# pcbSchematic.net
KiCad netlist of a schematic drawn in Altium Designer
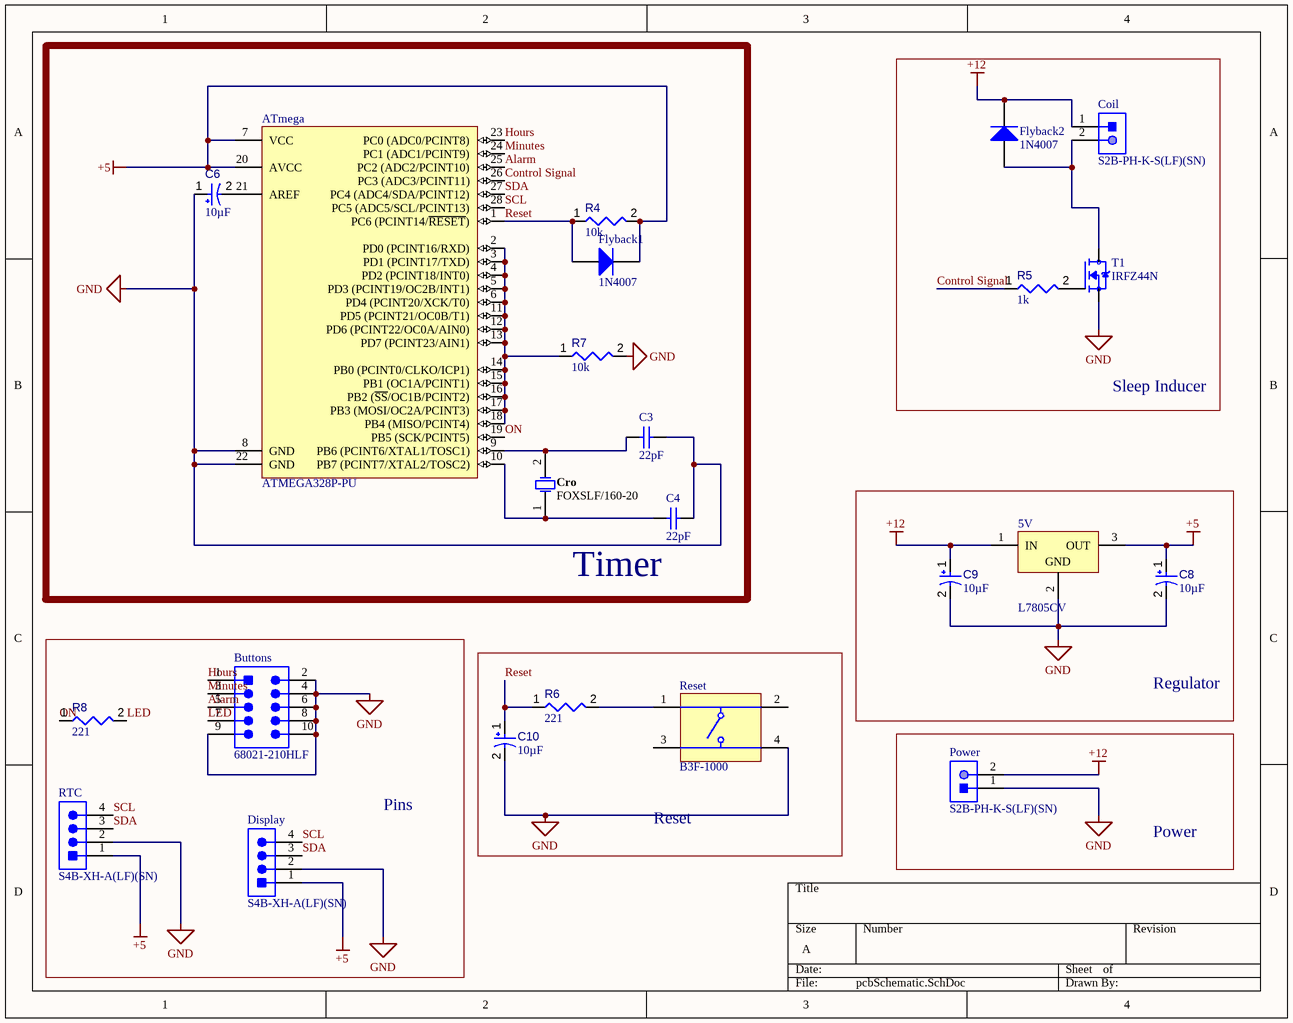
[diagram p0: pcbSchematic.SchDoc]

(export (version "E")
  (design (tool "Eeschema 10.0.6"))
  (components
    (comp (ref "5V")
      (value "L7805CV")
      (footprint "TO220")
      (description "Positive Voltage Regulator IC, 1.5 A, 5 V, 0 to 125 degC, 3-Pin TO-220, RoHS, Tube")
      (fields (field (name "MANUFACTURER") "STMicroelectronics"))
      (libsource (lib "Sithma") (part "PM-REG-L4940-SIL3"))
    )
    (comp (ref "ATmega")
      (value "ATMEGA328P-PU")
      (footprint "ATML-28P3")
      (fields (field (name "MANUFACTURER") "Atmel"))
      (libsource (lib "Sithma") (part "MC-8B-ATM48-IL28"))
    )
    (comp (ref "Buttons")
      (value "68021-210HLF")
      (footprint "FCI-68021-210HLF-10_V")
      (description "Male Header, Pitch 2.54 mm, 2 x 5 Position, Height 4.83 mm, Tail Length 3.05 mm, Bulk")
      (fields (field (name "MANUFACTURER") "FCI Electronics"))
      (libsource (lib "Sithma") (part "CN-2P-M-R10"))
    )
    (comp (ref "C3")
      (value "22pF")
      (footprint "KEMT-C315-THT-2")
      (description "Capacitor, Ceramic, 22 pF, +/-10 %, 100 V, -55 to 125 degC, 2-Pin THD, RoHS, Bulk")
      (libsource (lib "Altium Content Vault") (part "CAP-NP-2"))
    )
    (comp (ref "C4")
      (value "22pF")
      (footprint "KEMT-C315-THT-2")
      (description "Capacitor, Ceramic, 22 pF, +/-10 %, 100 V, -55 to 125 degC, 2-Pin THD, RoHS, Bulk")
      (libsource (lib "Altium Content Vault") (part "CAP-NP-2"))
    )
    (comp (ref "C6")
      (value "10µF")
      (footprint "CAPPR55-200-1100X500X1200")
      (description "Aluminum Electrolytic Capacitor, 10 uF, +/- 20%, 50 V, -40 to 85 degC, 2-Pin THD, RoHS, Bulk")
      (fields (field (name "MANUFACTURER") "Panasonic") (field (name "TOLERANCE") "20%"))
      (libsource (lib "") (part "CAP-P-2_1"))
    )
    (comp (ref "C8")
      (value "10µF")
      (footprint "CAPPR55-200-1100X500X1200")
      (description "Aluminum Electrolytic Capacitor, 10 uF, +/- 20%, 50 V, -40 to 85 degC, 2-Pin THD, RoHS, Bulk")
      (fields (field (name "MANUFACTURER") "Panasonic") (field (name "TOLERANCE") "20%"))
      (libsource (lib "Sithma") (part "CAP-P-2"))
    )
    (comp (ref "C9")
      (value "10µF")
      (footprint "CAPPR55-200-1100X500X1200")
      (description "Aluminum Electrolytic Capacitor, 10 uF, +/- 20%, 50 V, -40 to 85 degC, 2-Pin THD, RoHS, Bulk")
      (fields (field (name "MANUFACTURER") "Panasonic") (field (name "TOLERANCE") "20%"))
      (libsource (lib "Sithma") (part "CAP-P-2"))
    )
    (comp (ref "C10")
      (value "10µF")
      (footprint "CAPPR55-200-1100X500X1200")
      (description "Aluminum Electrolytic Capacitor, 10 uF, +/- 20%, 50 V, -40 to 85 degC, 2-Pin THD, RoHS, Bulk")
      (fields (field (name "MANUFACTURER") "Panasonic") (field (name "TOLERANCE") "20%"))
      (libsource (lib "Sithma") (part "CAP-P-2"))
    )
    (comp (ref "Coil")
      (value "S2B-PH-K-S(LF)(SN)")
      (footprint "JST-S2B-PH-K-S_V")
      (fields (field (name "MANUFACTURER") "Japan Solderless Terminals"))
      (libsource (lib "Sithma") (part "CN-1P-M-R2"))
    )
    (comp (ref "Cro")
      (value "FOXSLF/160-20")
      (footprint "FOX-FOXSLF160-20")
      (fields (field (name "MANUFACTURER") "FOX Electronics") (field (name "TOLERANCE") "50ppm"))
      (libsource (lib "Sithma") (part "XTAL-1-2-2"))
    )
    (comp (ref "Display")
      (value "S4B-XH-A(LF)(SN)")
      (footprint "JST-S4B-XH-A(LF)(SN)_V")
      (fields (field (name "MANUFACTURER") "JST"))
      (libsource (lib "Sithma") (part "CN-1P-M-R4"))
    )
    (comp (ref "Flyback1")
      (value "1N4007")
      (footprint "FAIR-DO-41-2")
      (description "General Purpose Rectifier, 1.1 V, 1.0 A, -55 to 175 degC, 2-Pin DO-41, RoHS, Tape and Reel")
      (fields (field (name "MANUFACTURER") "Fairchild"))
      (libsource (lib "Sithma") (part "KESE-D_K1A2-2"))
    )
    (comp (ref "Flyback2")
      (value "1N4007")
      (footprint "FAIR-DO-41-2")
      (description "General Purpose Rectifier, 1.1 V, 1.0 A, -55 to 175 degC, 2-Pin DO-41, RoHS, Tape and Reel")
      (fields (field (name "MANUFACTURER") "Fairchild"))
      (libsource (lib "Sithma") (part "KESE-D_K1A2-2"))
    )
    (comp (ref "Power")
      (value "S2B-PH-K-S(LF)(SN)")
      (footprint "JST-S2B-PH-K-S_V")
      (fields (field (name "MANUFACTURER") "Japan Solderless Terminals"))
      (libsource (lib "") (part "CN-1P-M-R2_1"))
    )
    (comp (ref "R4")
      (value "10k")
      (footprint "RESA60-630X240")
      (description "Axial Resistor, 10 KOhm, +/- 1%, 0.25 W, -55 to 155 degC, 2-Pin THD, RoHS, Bulk")
      (fields (field (name "TOLERANCE") "1%") (field (name "POWER") "250mW"))
      (libsource (lib "Sithma") (part "RES-2"))
    )
    (comp (ref "R5")
      (value "1k")
      (footprint "RESA60-630X240")
      (description "Axial Resistor, 1 KOhm, +/- 1%, 250 mW, -55 to 155 degC, 2-Pin THD, RoHS, Bulk")
      (fields (field (name "TOLERANCE") "1%") (field (name "POWER") "250mW"))
      (libsource (lib "Sithma") (part "RES-2"))
    )
    (comp (ref "R6")
      (value "221")
      (footprint "RESA60-630X240")
      (description "Axial Resistor, 221 Ohm, +/- 1%, 250 mW, -55 to 155 degC, 2-Pin THD, RoHS, Bulk")
      (fields (field (name "POWER") "250mW") (field (name "TOLERANCE") "1%"))
      (libsource (lib "Sithma") (part "RES-2"))
    )
    (comp (ref "R7")
      (value "10k")
      (footprint "RESA60-630X240")
      (description "Axial Resistor, 10 KOhm, +/- 1%, 0.25 W, -55 to 155 degC, 2-Pin THD, RoHS, Bulk")
      (fields (field (name "TOLERANCE") "1%") (field (name "POWER") "250mW"))
      (libsource (lib "Sithma") (part "RES-2"))
    )
    (comp (ref "R8")
      (value "221")
      (footprint "RESA60-630X240")
      (description "Axial Resistor, 221 Ohm, +/- 1%, 250 mW, -55 to 155 degC, 2-Pin THD, RoHS, Bulk")
      (fields (field (name "POWER") "250mW") (field (name "TOLERANCE") "1%"))
      (libsource (lib "Sithma") (part "RES-2"))
    )
    (comp (ref "Reset")
      (value "B3F-1000")
      (footprint "OMRON-B3F-1000-4_V")
      (description "Tactile Switch, SPST-NO, 0.05 A, 24 V, -25 to 70 degC, 4-Pin THD, RoHS, Bulk")
      (fields (field (name "MANUFACTURER") "Omron Electronic Components"))
      (libsource (lib "Sithma") (part "SW-SPST-4_A"))
    )
    (comp (ref "RTC")
      (value "S4B-XH-A(LF)(SN)")
      (footprint "JST-S4B-XH-A(LF)(SN)_V")
      (fields (field (name "MANUFACTURER") "JST"))
      (libsource (lib "Sithma") (part "CN-1P-M-R4"))
    )
    (comp (ref "T1")
      (value "IRFZ44N")
      (footprint "TO254P1016X419X2286-3")
      (description "N-Channel 55 V 49A (Tc) 94W (Tc) Through Hole TO-220AB")
      (fields (field (name "MF") "Infineon Technologies"))
      (libsource (lib "Sithma") (part "IRFZ44N"))
    )
  )
  (nets
    (net (code "1") (name "+5") (class "Default")
      (node (ref "5V") (pin "3") (pinfunction "OUT_3") (pintype "power_in"))
      (node (ref "ATmega") (pin "20") (pinfunction "AVCC_20") (pintype "power_in"))
      (node (ref "ATmega") (pin "7") (pinfunction "VCC_7") (pintype "power_in"))
      (node (ref "C8") (pin "1") (pinfunction "1_1") (pintype "passive"))
      (node (ref "Display") (pin "1") (pinfunction "1_1") (pintype "passive"))
      (node (ref "Flyback1") (pin "1") (pinfunction "K_1") (pintype "passive"))
      (node (ref "R4") (pin "2") (pinfunction "2_2") (pintype "passive"))
      (node (ref "RTC") (pin "1") (pinfunction "1_1") (pintype "passive"))
    )
    (net (code "2") (name "+12") (class "Default")
      (node (ref "5V") (pin "1") (pinfunction "IN_1") (pintype "power_in"))
      (node (ref "C9") (pin "1") (pinfunction "1_1") (pintype "passive"))
      (node (ref "Coil") (pin "1") (pinfunction "1_1") (pintype "passive"))
      (node (ref "Flyback2") (pin "1") (pinfunction "K_1") (pintype "passive"))
      (node (ref "Power") (pin "2") (pinfunction "2_2") (pintype "passive"))
    )
    (net (code "3") (name "/Alarm") (class "Default")
      (node (ref "ATmega") (pin "25") (pinfunction "PC2_(ADC2/PCINT10)_25") (pintype "bidirectional"))
      (node (ref "Buttons") (pin "5") (pinfunction "5_5") (pintype "passive"))
    )
    (net (code "4") (name "/Control Signal") (class "Default")
      (node (ref "ATmega") (pin "26") (pinfunction "PC3_(ADC3/PCINT11)_26") (pintype "bidirectional"))
      (node (ref "R5") (pin "1") (pinfunction "1_1") (pintype "passive"))
    )
    (net (code "5") (name "/Hours") (class "Default")
      (node (ref "ATmega") (pin "23") (pinfunction "PC0_(ADC0/PCINT8)_23") (pintype "bidirectional"))
      (node (ref "Buttons") (pin "1") (pinfunction "1_1") (pintype "passive"))
    )
    (net (code "6") (name "/LED") (class "Default")
      (node (ref "Buttons") (pin "7") (pinfunction "7_7") (pintype "passive"))
      (node (ref "R8") (pin "2") (pinfunction "2_2") (pintype "passive"))
    )
    (net (code "7") (name "/Minutes") (class "Default")
      (node (ref "ATmega") (pin "24") (pinfunction "PC1_(ADC1/PCINT9)_24") (pintype "bidirectional"))
      (node (ref "Buttons") (pin "3") (pinfunction "3_3") (pintype "passive"))
    )
    (net (code "8") (name "/ON") (class "Default")
      (node (ref "ATmega") (pin "19") (pinfunction "PB5_(SCK/PCINT5)_19") (pintype "bidirectional"))
      (node (ref "R8") (pin "1") (pinfunction "1_1") (pintype "passive"))
    )
    (net (code "9") (name "/Reset") (class "Default")
      (node (ref "ATmega") (pin "1") (pinfunction "PC6_(PCINT14/~{RESET})_1") (pintype "bidirectional"))
      (node (ref "C10") (pin "1") (pinfunction "1_1") (pintype "passive"))
      (node (ref "Flyback1") (pin "2") (pinfunction "A_2") (pintype "passive"))
      (node (ref "R4") (pin "1") (pinfunction "1_1") (pintype "passive"))
      (node (ref "R6") (pin "1") (pinfunction "1_1") (pintype "passive"))
    )
    (net (code "10") (name "/SCL") (class "Default")
      (node (ref "ATmega") (pin "28") (pinfunction "PC5_(ADC5/SCL/PCINT13)_28") (pintype "bidirectional"))
      (node (ref "Display") (pin "4") (pinfunction "4_4") (pintype "passive"))
      (node (ref "RTC") (pin "4") (pinfunction "4_4") (pintype "passive"))
    )
    (net (code "11") (name "/SDA") (class "Default")
      (node (ref "ATmega") (pin "27") (pinfunction "PC4_(ADC4/SDA/PCINT12)_27") (pintype "bidirectional"))
      (node (ref "Display") (pin "3") (pinfunction "3_3") (pintype "passive"))
      (node (ref "RTC") (pin "3") (pinfunction "3_3") (pintype "passive"))
    )
    (net (code "12") (name "GND") (class "Default")
      (node (ref "5V") (pin "2") (pinfunction "GND_2") (pintype "power_in"))
      (node (ref "ATmega") (pin "22") (pinfunction "GND_22") (pintype "power_in"))
      (node (ref "ATmega") (pin "8") (pinfunction "GND_8") (pintype "power_in"))
      (node (ref "Buttons") (pin "10") (pinfunction "10_10") (pintype "passive"))
      (node (ref "Buttons") (pin "2") (pinfunction "2_2") (pintype "passive"))
      (node (ref "Buttons") (pin "4") (pinfunction "4_4") (pintype "passive"))
      (node (ref "Buttons") (pin "6") (pinfunction "6_6") (pintype "passive"))
      (node (ref "Buttons") (pin "8") (pinfunction "8_8") (pintype "passive"))
      (node (ref "Buttons") (pin "9") (pinfunction "9_9") (pintype "passive"))
      (node (ref "C10") (pin "2") (pinfunction "2_2") (pintype "passive"))
      (node (ref "C3") (pin "2") (pinfunction "2_2") (pintype "passive"))
      (node (ref "C4") (pin "2") (pinfunction "2_2") (pintype "passive"))
      (node (ref "C6") (pin "1") (pinfunction "1_1") (pintype "passive"))
      (node (ref "C8") (pin "2") (pinfunction "2_2") (pintype "passive"))
      (node (ref "C9") (pin "2") (pinfunction "2_2") (pintype "passive"))
      (node (ref "Display") (pin "2") (pinfunction "2_2") (pintype "passive"))
      (node (ref "Power") (pin "1") (pinfunction "1_1") (pintype "passive"))
      (node (ref "R7") (pin "2") (pinfunction "2_2") (pintype "passive"))
      (node (ref "RTC") (pin "2") (pinfunction "2_2") (pintype "passive"))
      (node (ref "Reset") (pin "4") (pinfunction "4_4") (pintype "passive"))
      (node (ref "T1") (pin "3") (pinfunction "S_3") (pintype "passive"))
    )
    (net (code "13") (name "Net-(ATmega-AREF)") (class "Default")
      (node (ref "ATmega") (pin "21") (pinfunction "AREF_21") (pintype "power_in"))
      (node (ref "C6") (pin "2") (pinfunction "2_2") (pintype "passive"))
    )
    (net (code "14") (name "Net-(ATmega-PB0_(PCINT0{slash}CLKO{slash}ICP1))") (class "Default")
      (node (ref "ATmega") (pin "11") (pinfunction "PD5_(PCINT21/OC0B/T1)_11") (pintype "bidirectional"))
      (node (ref "ATmega") (pin "12") (pinfunction "PD6_(PCINT22/OC0A/AIN0)_12") (pintype "bidirectional"))
      (node (ref "ATmega") (pin "13") (pinfunction "PD7_(PCINT23/AIN1)_13") (pintype "bidirectional"))
      (node (ref "ATmega") (pin "14") (pinfunction "PB0_(PCINT0/CLKO/ICP1)_14") (pintype "bidirectional"))
      (node (ref "ATmega") (pin "15") (pinfunction "PB1_(OC1A/PCINT1)_15") (pintype "bidirectional"))
      (node (ref "ATmega") (pin "16") (pinfunction "PB2_(~{SS}/OC1B/PCINT2)_16") (pintype "bidirectional"))
      (node (ref "ATmega") (pin "17") (pinfunction "PB3_(MOSI/OC2A/PCINT3)_17") (pintype "bidirectional"))
      (node (ref "ATmega") (pin "18") (pinfunction "PB4_(MISO/PCINT4)_18") (pintype "bidirectional"))
      (node (ref "ATmega") (pin "2") (pinfunction "PD0_(PCINT16/RXD)_2") (pintype "bidirectional"))
      (node (ref "ATmega") (pin "3") (pinfunction "PD1_(PCINT17/TXD)_3") (pintype "bidirectional"))
      (node (ref "ATmega") (pin "4") (pinfunction "PD2_(PCINT18/INT0)_4") (pintype "bidirectional"))
      (node (ref "ATmega") (pin "5") (pinfunction "PD3_(PCINT19/OC2B/INT1)_5") (pintype "bidirectional"))
      (node (ref "ATmega") (pin "6") (pinfunction "PD4_(PCINT20/XCK/T0)_6") (pintype "bidirectional"))
      (node (ref "R7") (pin "1") (pinfunction "1_1") (pintype "passive"))
    )
    (net (code "15") (name "Net-(ATmega-PB6_(PCINT6{slash}XTAL1{slash}TOSC1))") (class "Default")
      (node (ref "ATmega") (pin "9") (pinfunction "PB6_(PCINT6/XTAL1/TOSC1)_9") (pintype "bidirectional"))
      (node (ref "C3") (pin "1") (pinfunction "1_1") (pintype "passive"))
      (node (ref "Cro") (pin "2") (pinfunction "2_2") (pintype "passive"))
    )
    (net (code "16") (name "Net-(ATmega-PB7_(PCINT7{slash}XTAL2{slash}TOSC2))") (class "Default")
      (node (ref "ATmega") (pin "10") (pinfunction "PB7_(PCINT7/XTAL2/TOSC2)_10") (pintype "bidirectional"))
      (node (ref "C4") (pin "1") (pinfunction "1_1") (pintype "passive"))
      (node (ref "Cro") (pin "1") (pinfunction "1_1") (pintype "passive"))
    )
    (net (code "17") (name "Net-(Flyback2-A)") (class "Default")
      (node (ref "Coil") (pin "2") (pinfunction "2_2") (pintype "passive"))
      (node (ref "Flyback2") (pin "2") (pinfunction "A_2") (pintype "passive"))
      (node (ref "T1") (pin "2") (pinfunction "D_2") (pintype "passive"))
    )
    (net (code "18") (name "Net-(R6-Pad2)") (class "Default")
      (node (ref "R6") (pin "2") (pinfunction "2_2") (pintype "passive"))
      (node (ref "Reset") (pin "1") (pinfunction "1_1") (pintype "passive"))
    )
    (net (code "19") (name "Net-(T1-G)") (class "Default")
      (node (ref "R5") (pin "2") (pinfunction "2_2") (pintype "passive"))
      (node (ref "T1") (pin "1") (pinfunction "G_1") (pintype "passive"))
    )
    (net (code "20") (name "unconnected-(Reset-Pad2)") (class "Default")
      (node (ref "Reset") (pin "2") (pinfunction "2_2") (pintype "passive"))
    )
    (net (code "21") (name "unconnected-(Reset-Pad3)") (class "Default")
      (node (ref "Reset") (pin "3") (pinfunction "3_3") (pintype "passive"))
    )
  )
)
